# VoltageRegulatorShield.net
KiCad netlist of a schematic drawn in Altium Designer
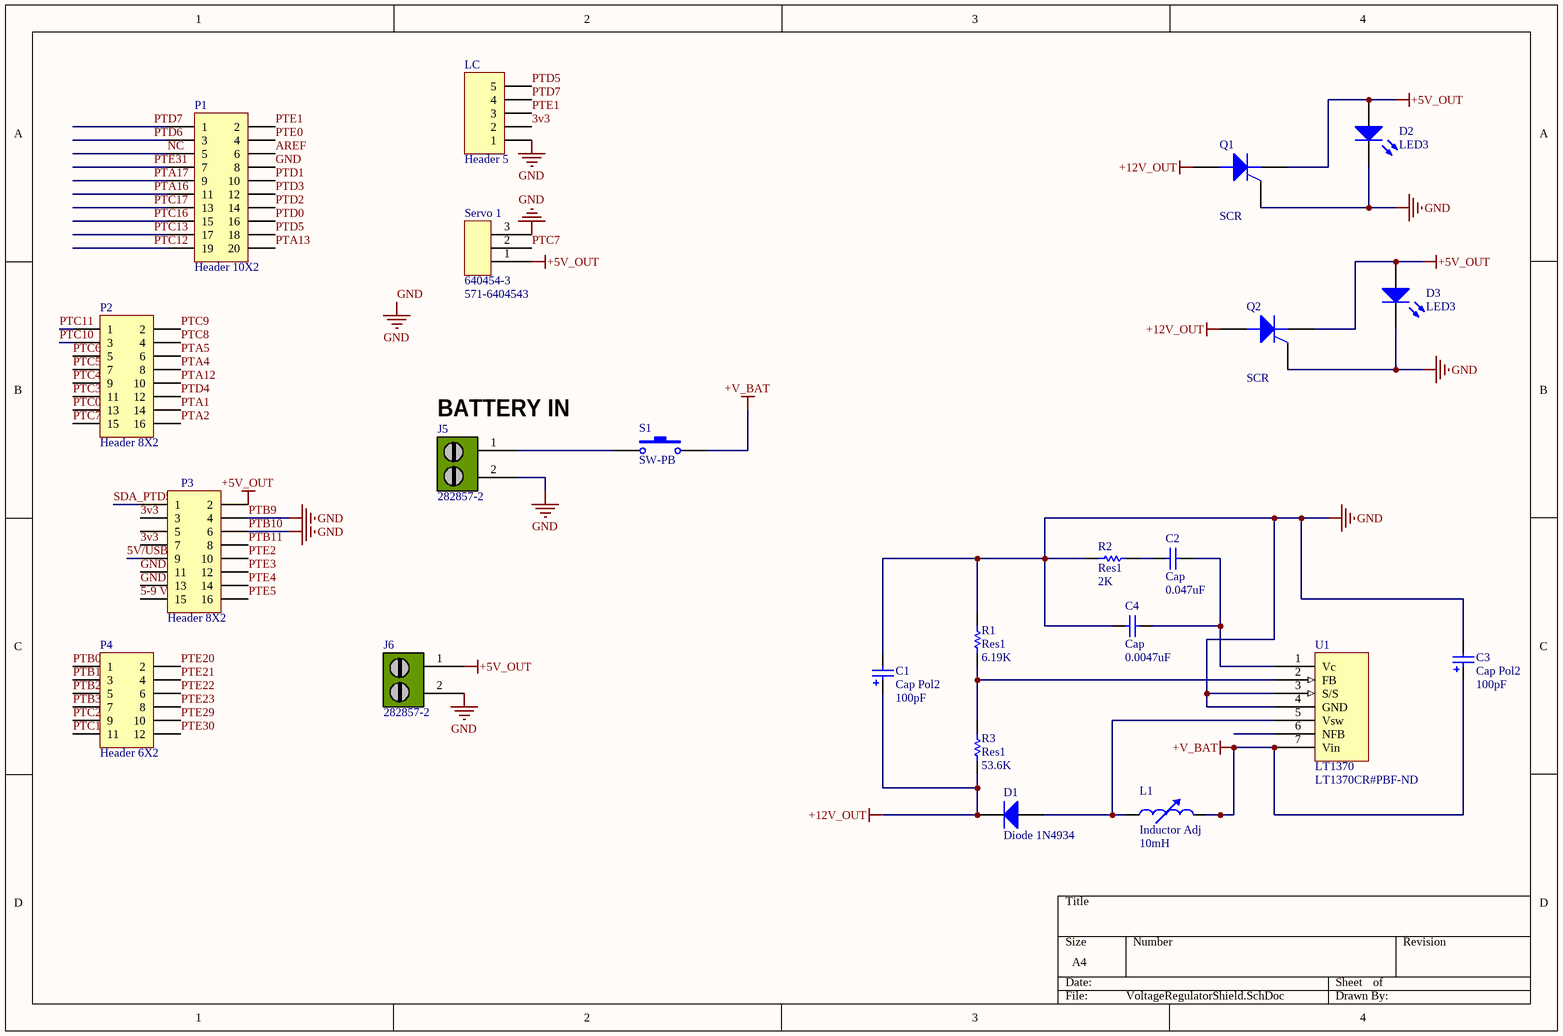
[diagram p0: VoltageRegulatorShield.SchDoc]

(export (version "E")
  (design (tool "Eeschema 10.0.6"))
  (components
    (comp (ref "C1")
      (value "Cap Pol2")
      (footprint "POLAR0.8")
      (description "Polarized Capacitor (Axial)")
      (fields (field (name "ALTIUM_VALUE") "100pF") (field (name "PUBLISHER") "Altium Limited"))
      (libsource (lib "Miscellaneous Devices") (part "Cap Pol2"))
    )
    (comp (ref "C2")
      (value "Cap")
      (footprint "RAD-0.3")
      (description "Capacitor")
      (fields (field (name "ALTIUM_VALUE") "0.047uF") (field (name "PUBLISHER") "Altium Limited"))
      (libsource (lib "Miscellaneous Devices") (part "Cap"))
    )
    (comp (ref "C3")
      (value "Cap Pol2")
      (footprint "POLAR0.8")
      (description "Polarized Capacitor (Axial)")
      (fields (field (name "ALTIUM_VALUE") "100pF") (field (name "PUBLISHER") "Altium Limited"))
      (libsource (lib "Miscellaneous Devices") (part "Cap Pol2"))
    )
    (comp (ref "C4")
      (value "Cap")
      (footprint "RAD-0.3")
      (description "Capacitor")
      (fields (field (name "ALTIUM_VALUE") "0.0047uF") (field (name "PUBLISHER") "Altium Limited"))
      (libsource (lib "Miscellaneous Devices") (part "Cap"))
    )
    (comp (ref "D1")
      (value "Diode 1N4934")
      (footprint "DO-41")
      (description "1 Amp Fast Recovery Rectifier")
      (fields (field (name "PUBLISHER") "Altium Limited"))
      (libsource (lib "Miscellaneous Devices") (part "Diode 1N4934"))
    )
    (comp (ref "D2")
      (value "LED3")
      (footprint "3.5X2.8X1.9")
      (description "Typical BLUE SiC LED")
      (fields (field (name "PUBLISHER") "Altium Limited"))
      (libsource (lib "Miscellaneous Devices") (part "LED3"))
    )
    (comp (ref "D3")
      (value "LED3")
      (footprint "3.5X2.8X1.9")
      (description "Typical BLUE SiC LED")
      (fields (field (name "PUBLISHER") "Altium Limited"))
      (libsource (lib "Miscellaneous Devices") (part "LED3"))
    )
    (comp (ref "J5")
      (value "282857-2")
      (footprint "282857-2")
      (description "TERM BLOCK 2POS SIDE ENT 5.08MM")
      (fields (field (name "MANUFACTURER") "TE Connectivity") (field (name "VOLTAGE") "300V"))
      (libsource (lib "eConnector") (part "282857-2"))
    )
    (comp (ref "J6")
      (value "282857-2")
      (footprint "282857-2")
      (description "TERM BLOCK 2POS SIDE ENT 5.08MM")
      (fields (field (name "MANUFACTURER") "TE Connectivity") (field (name "VOLTAGE") "300V"))
      (libsource (lib "eConnector") (part "282857-2"))
    )
    (comp (ref "L1")
      (value "Inductor Adj")
      (footprint "AXIAL-0.8")
      (description "Adjustable Inductor")
      (fields (field (name "ALTIUM_VALUE") "10mH") (field (name "PUBLISHER") "Altium Limited"))
      (libsource (lib "Miscellaneous Devices") (part "Inductor Adj"))
    )
    (comp (ref "LC")
      (value "Header 5")
      (footprint "HDR1X5")
      (description "Header, 5-Pin")
      (fields (field (name "PUBLISHER") "Altium Limited"))
      (libsource (lib "Miscellaneous Connectors") (part "Header 5"))
    )
    (comp (ref "P1")
      (value "Header 10X2")
      (footprint "HDR2X10")
      (description "Header, 10-Pin, Dual row")
      (fields (field (name "PUBLISHER") "Altium Limited"))
      (libsource (lib "Miscellaneous Connectors") (part "Header 10X2"))
    )
    (comp (ref "P2")
      (value "Header 8X2")
      (footprint "HDR2X8")
      (description "Header, 8-Pin, Dual row")
      (fields (field (name "PUBLISHER") "Altium Limited"))
      (libsource (lib "Miscellaneous Connectors") (part "Header 8X2"))
    )
    (comp (ref "P3")
      (value "Header 8X2")
      (footprint "HDR2X8")
      (description "Header, 8-Pin, Dual row")
      (fields (field (name "PUBLISHER") "Altium Limited"))
      (libsource (lib "Miscellaneous Connectors") (part "Header 8X2"))
    )
    (comp (ref "P4")
      (value "Header 6X2")
      (footprint "HDR2X6")
      (description "Header, 6-Pin, Dual row")
      (fields (field (name "PUBLISHER") "Altium Limited"))
      (libsource (lib "Miscellaneous Connectors") (part "Header 6X2"))
    )
    (comp (ref "Q1")
      (value "SCR")
      (footprint "TO-220-AB")
      (description "Silicon Controlled Rectifier")
      (fields (field (name "PUBLISHER") "Altium Limited"))
      (libsource (lib "Miscellaneous Devices") (part "SCR"))
    )
    (comp (ref "Q2")
      (value "SCR")
      (footprint "TO-220-AB")
      (description "Silicon Controlled Rectifier")
      (fields (field (name "PUBLISHER") "Altium Limited"))
      (libsource (lib "Miscellaneous Devices") (part "SCR"))
    )
    (comp (ref "R1")
      (value "Res1")
      (footprint "AXIAL-0.3")
      (description "Resistor")
      (fields (field (name "ALTIUM_VALUE") "6.19K") (field (name "PUBLISHER") "Altium Limited"))
      (libsource (lib "Miscellaneous Devices") (part "Res1"))
    )
    (comp (ref "R2")
      (value "Res1")
      (footprint "AXIAL-0.3")
      (description "Resistor")
      (fields (field (name "ALTIUM_VALUE") "2K") (field (name "PUBLISHER") "Altium Limited"))
      (libsource (lib "Miscellaneous Devices") (part "Res1"))
    )
    (comp (ref "R3")
      (value "Res1")
      (footprint "AXIAL-0.3")
      (description "Resistor")
      (fields (field (name "ALTIUM_VALUE") "53.6K") (field (name "PUBLISHER") "Altium Limited"))
      (libsource (lib "Miscellaneous Devices") (part "Res1"))
    )
    (comp (ref "S1")
      (value "SW-PB")
      (footprint "SPST-2")
      (description "Switch")
      (fields (field (name "PUBLISHER") "Altium Limited"))
      (libsource (lib "Miscellaneous Devices") (part "SW-PB"))
    )
    (comp (ref "Servo 1")
      (value "640454-3")
      (footprint "6404543")
      (description "Headers & Wire Housings POLARIZED HEADER 3P Straight Post tin")
      (fields (field (name "SUPPLIER PART NUMBER 1") "571-6404543"))
      (libsource (lib "TE_Connectors") (part "640454-3"))
    )
    (comp (ref "U1")
      (value "LT1370")
      (footprint "DDPak7")
      (fields (field (name "SUPPLIER PART NUMBER 1") "LT1370CR#PBF-ND"))
      (libsource (lib "Switching_Regulators") (part "LT1370"))
    )
  )
  (nets
    (net (code "1") (name "+5V_OUT") (class "Default")
      (node (ref "D2") (pin "1") (pinfunction "A_1") (pintype "passive"))
      (node (ref "D3") (pin "1") (pinfunction "A_1") (pintype "passive"))
      (node (ref "J6") (pin "1") (pinfunction "1_1") (pintype "passive"))
      (node (ref "P3") (pin "2") (pinfunction "2_2") (pintype "passive"))
      (node (ref "Q1") (pin "3") (pinfunction "K_3") (pintype "passive"))
      (node (ref "Q2") (pin "3") (pinfunction "K_3") (pintype "passive"))
      (node (ref "Servo 1") (pin "1") (pinfunction "1_1") (pintype "passive"))
    )
    (net (code "2") (name "+12V_OUT") (class "Default")
      (node (ref "C1") (pin "1") (pinfunction "1_1") (pintype "passive"))
      (node (ref "D1") (pin "2") (pinfunction "K_2") (pintype "passive"))
      (node (ref "Q1") (pin "1") (pinfunction "A_1") (pintype "passive"))
      (node (ref "Q2") (pin "1") (pinfunction "A_1") (pintype "passive"))
      (node (ref "R3") (pin "2") (pinfunction "2_2") (pintype "passive"))
    )
    (net (code "3") (name "+V_BAT") (class "Default")
      (node (ref "C3") (pin "1") (pinfunction "1_1") (pintype "passive"))
      (node (ref "L1") (pin "2") (pinfunction "2_2") (pintype "passive"))
      (node (ref "S1") (pin "2") (pinfunction "2_2") (pintype "passive"))
      (node (ref "U1") (pin "7") (pinfunction "Vin_7") (pintype "power_in"))
    )
    (net (code "4") (name "/3v3") (class "Default")
      (node (ref "LC") (pin "2") (pinfunction "2_2") (pintype "passive"))
      (node (ref "P3") (pin "3") (pinfunction "3_3") (pintype "passive"))
      (node (ref "P3") (pin "7") (pinfunction "7_7") (pintype "passive"))
    )
    (net (code "5") (name "/5-9 Vin") (class "Default")
      (node (ref "P3") (pin "15") (pinfunction "15_15") (pintype "passive"))
    )
    (net (code "6") (name "/5V{slash}USB") (class "Default")
      (node (ref "P3") (pin "9") (pinfunction "9_9") (pintype "passive"))
    )
    (net (code "7") (name "/AREF") (class "Default")
      (node (ref "P1") (pin "6") (pinfunction "6_6") (pintype "passive"))
    )
    (net (code "8") (name "/NC") (class "Default")
      (node (ref "P1") (pin "5") (pinfunction "5_5") (pintype "passive"))
    )
    (net (code "9") (name "/PTA1") (class "Default")
      (node (ref "P2") (pin "14") (pinfunction "14_14") (pintype "passive"))
    )
    (net (code "10") (name "/PTA2") (class "Default")
      (node (ref "P2") (pin "16") (pinfunction "16_16") (pintype "passive"))
    )
    (net (code "11") (name "/PTA4") (class "Default")
      (node (ref "P2") (pin "8") (pinfunction "8_8") (pintype "passive"))
    )
    (net (code "12") (name "/PTA5") (class "Default")
      (node (ref "P2") (pin "6") (pinfunction "6_6") (pintype "passive"))
    )
    (net (code "13") (name "/PTA12") (class "Default")
      (node (ref "P2") (pin "10") (pinfunction "10_10") (pintype "passive"))
    )
    (net (code "14") (name "/PTA13") (class "Default")
      (node (ref "P1") (pin "20") (pinfunction "20_20") (pintype "passive"))
    )
    (net (code "15") (name "/PTA16") (class "Default")
      (node (ref "P1") (pin "11") (pinfunction "11_11") (pintype "passive"))
    )
    (net (code "16") (name "/PTA17") (class "Default")
      (node (ref "P1") (pin "9") (pinfunction "9_9") (pintype "passive"))
    )
    (net (code "17") (name "/PTB0") (class "Default")
      (node (ref "P4") (pin "1") (pinfunction "1_1") (pintype "passive"))
    )
    (net (code "18") (name "/PTB1") (class "Default")
      (node (ref "P4") (pin "3") (pinfunction "3_3") (pintype "passive"))
    )
    (net (code "19") (name "/PTB2") (class "Default")
      (node (ref "P4") (pin "5") (pinfunction "5_5") (pintype "passive"))
    )
    (net (code "20") (name "/PTB3") (class "Default")
      (node (ref "P4") (pin "7") (pinfunction "7_7") (pintype "passive"))
    )
    (net (code "21") (name "/PTB11") (class "Default")
      (node (ref "P3") (pin "8") (pinfunction "8_8") (pintype "passive"))
    )
    (net (code "22") (name "/PTC0") (class "Default")
      (node (ref "P2") (pin "13") (pinfunction "13_13") (pintype "passive"))
    )
    (net (code "23") (name "/PTC1") (class "Default")
      (node (ref "P4") (pin "11") (pinfunction "11_11") (pintype "passive"))
    )
    (net (code "24") (name "/PTC2") (class "Default")
      (node (ref "P4") (pin "9") (pinfunction "9_9") (pintype "passive"))
    )
    (net (code "25") (name "/PTC3") (class "Default")
      (node (ref "P2") (pin "11") (pinfunction "11_11") (pintype "passive"))
    )
    (net (code "26") (name "/PTC4") (class "Default")
      (node (ref "P2") (pin "9") (pinfunction "9_9") (pintype "passive"))
    )
    (net (code "27") (name "/PTC5") (class "Default")
      (node (ref "P2") (pin "7") (pinfunction "7_7") (pintype "passive"))
    )
    (net (code "28") (name "/PTC6") (class "Default")
      (node (ref "P2") (pin "5") (pinfunction "5_5") (pintype "passive"))
    )
    (net (code "29") (name "/PTC7") (class "Default")
      (node (ref "P2") (pin "15") (pinfunction "15_15") (pintype "passive"))
      (node (ref "Servo 1") (pin "2") (pinfunction "2_2") (pintype "passive"))
    )
    (net (code "30") (name "/PTC8") (class "Default")
      (node (ref "P2") (pin "4") (pinfunction "4_4") (pintype "passive"))
    )
    (net (code "31") (name "/PTC9") (class "Default")
      (node (ref "P2") (pin "2") (pinfunction "2_2") (pintype "passive"))
    )
    (net (code "32") (name "/PTC10") (class "Default")
      (node (ref "P2") (pin "3") (pinfunction "3_3") (pintype "passive"))
    )
    (net (code "33") (name "/PTC11") (class "Default")
      (node (ref "P2") (pin "1") (pinfunction "1_1") (pintype "passive"))
    )
    (net (code "34") (name "/PTC12") (class "Default")
      (node (ref "P1") (pin "19") (pinfunction "19_19") (pintype "passive"))
    )
    (net (code "35") (name "/PTC13") (class "Default")
      (node (ref "P1") (pin "17") (pinfunction "17_17") (pintype "passive"))
    )
    (net (code "36") (name "/PTC16") (class "Default")
      (node (ref "P1") (pin "15") (pinfunction "15_15") (pintype "passive"))
    )
    (net (code "37") (name "/PTC17") (class "Default")
      (node (ref "P1") (pin "13") (pinfunction "13_13") (pintype "passive"))
    )
    (net (code "38") (name "/PTD0") (class "Default")
      (node (ref "P1") (pin "16") (pinfunction "16_16") (pintype "passive"))
    )
    (net (code "39") (name "/PTD1") (class "Default")
      (node (ref "P1") (pin "10") (pinfunction "10_10") (pintype "passive"))
    )
    (net (code "40") (name "/PTD2") (class "Default")
      (node (ref "P1") (pin "14") (pinfunction "14_14") (pintype "passive"))
    )
    (net (code "41") (name "/PTD3") (class "Default")
      (node (ref "P1") (pin "12") (pinfunction "12_12") (pintype "passive"))
    )
    (net (code "42") (name "/PTD4") (class "Default")
      (node (ref "P2") (pin "12") (pinfunction "12_12") (pintype "passive"))
    )
    (net (code "43") (name "/PTD5") (class "Default")
      (node (ref "LC") (pin "5") (pinfunction "5_5") (pintype "passive"))
      (node (ref "P1") (pin "18") (pinfunction "18_18") (pintype "passive"))
    )
    (net (code "44") (name "/PTD6") (class "Default")
      (node (ref "P1") (pin "3") (pinfunction "3_3") (pintype "passive"))
    )
    (net (code "45") (name "/PTD7") (class "Default")
      (node (ref "LC") (pin "4") (pinfunction "4_4") (pintype "passive"))
      (node (ref "P1") (pin "1") (pinfunction "1_1") (pintype "passive"))
    )
    (net (code "46") (name "/PTE0") (class "Default")
      (node (ref "P1") (pin "4") (pinfunction "4_4") (pintype "passive"))
    )
    (net (code "47") (name "/PTE1") (class "Default")
      (node (ref "LC") (pin "3") (pinfunction "3_3") (pintype "passive"))
      (node (ref "P1") (pin "2") (pinfunction "2_2") (pintype "passive"))
    )
    (net (code "48") (name "/PTE2") (class "Default")
      (node (ref "P3") (pin "10") (pinfunction "10_10") (pintype "passive"))
    )
    (net (code "49") (name "/PTE3") (class "Default")
      (node (ref "P3") (pin "12") (pinfunction "12_12") (pintype "passive"))
    )
    (net (code "50") (name "/PTE4") (class "Default")
      (node (ref "P3") (pin "14") (pinfunction "14_14") (pintype "passive"))
    )
    (net (code "51") (name "/PTE5") (class "Default")
      (node (ref "P3") (pin "16") (pinfunction "16_16") (pintype "passive"))
    )
    (net (code "52") (name "/PTE20") (class "Default")
      (node (ref "P4") (pin "2") (pinfunction "2_2") (pintype "passive"))
    )
    (net (code "53") (name "/PTE21") (class "Default")
      (node (ref "P4") (pin "4") (pinfunction "4_4") (pintype "passive"))
    )
    (net (code "54") (name "/PTE22") (class "Default")
      (node (ref "P4") (pin "6") (pinfunction "6_6") (pintype "passive"))
    )
    (net (code "55") (name "/PTE23") (class "Default")
      (node (ref "P4") (pin "8") (pinfunction "8_8") (pintype "passive"))
    )
    (net (code "56") (name "/PTE29") (class "Default")
      (node (ref "P4") (pin "10") (pinfunction "10_10") (pintype "passive"))
    )
    (net (code "57") (name "/PTE30") (class "Default")
      (node (ref "P4") (pin "12") (pinfunction "12_12") (pintype "passive"))
    )
    (net (code "58") (name "/PTE31") (class "Default")
      (node (ref "P1") (pin "7") (pinfunction "7_7") (pintype "passive"))
    )
    (net (code "59") (name "/SDA_PTD5") (class "Default")
      (node (ref "P3") (pin "1") (pinfunction "1_1") (pintype "passive"))
    )
    (net (code "60") (name "GND") (class "Default")
      (node (ref "C1") (pin "2") (pinfunction "2_2") (pintype "passive"))
      (node (ref "C3") (pin "2") (pinfunction "2_2") (pintype "passive"))
      (node (ref "C4") (pin "1") (pinfunction "1_1") (pintype "passive"))
      (node (ref "D2") (pin "2") (pinfunction "K_2") (pintype "passive"))
      (node (ref "D3") (pin "2") (pinfunction "K_2") (pintype "passive"))
      (node (ref "J5") (pin "2") (pinfunction "2_2") (pintype "passive"))
      (node (ref "J6") (pin "2") (pinfunction "2_2") (pintype "passive"))
      (node (ref "LC") (pin "1") (pinfunction "1_1") (pintype "passive"))
      (node (ref "P1") (pin "8") (pinfunction "8_8") (pintype "passive"))
      (node (ref "P3") (pin "11") (pinfunction "11_11") (pintype "passive"))
      (node (ref "P3") (pin "13") (pinfunction "13_13") (pintype "passive"))
      (node (ref "P3") (pin "4") (pinfunction "4_4") (pintype "passive"))
      (node (ref "P3") (pin "6") (pinfunction "6_6") (pintype "passive"))
      (node (ref "Q1") (pin "2") (pinfunction "G_2") (pintype "passive"))
      (node (ref "Q2") (pin "2") (pinfunction "G_2") (pintype "passive"))
      (node (ref "R1") (pin "1") (pinfunction "1_1") (pintype "passive"))
      (node (ref "R2") (pin "1") (pinfunction "1_1") (pintype "passive"))
      (node (ref "Servo 1") (pin "3") (pinfunction "3_3") (pintype "passive"))
      (node (ref "U1") (pin "3") (pinfunction "S/S_3") (pintype "input"))
      (node (ref "U1") (pin "4") (pinfunction "GND_4") (pintype "power_in"))
    )
    (net (code "61") (name "Net-(C2-Pad1)") (class "Default")
      (node (ref "C2") (pin "1") (pinfunction "1_1") (pintype "passive"))
      (node (ref "R2") (pin "2") (pinfunction "2_2") (pintype "passive"))
    )
    (net (code "62") (name "Net-(D1-A)") (class "Default")
      (node (ref "D1") (pin "1") (pinfunction "A_1") (pintype "passive"))
      (node (ref "L1") (pin "1") (pinfunction "1_1") (pintype "passive"))
      (node (ref "U1") (pin "5") (pinfunction "Vsw_5") (pintype "power_in"))
    )
    (net (code "63") (name "Net-(J5-Pad1)") (class "Default")
      (node (ref "J5") (pin "1") (pinfunction "1_1") (pintype "passive"))
      (node (ref "S1") (pin "1") (pinfunction "1_1") (pintype "passive"))
    )
    (net (code "64") (name "Net-(U1-FB)") (class "Default")
      (node (ref "R1") (pin "2") (pinfunction "2_2") (pintype "passive"))
      (node (ref "R3") (pin "1") (pinfunction "1_1") (pintype "passive"))
      (node (ref "U1") (pin "2") (pinfunction "FB_2") (pintype "input"))
    )
    (net (code "65") (name "Net-(U1-Vc)") (class "Default")
      (node (ref "C2") (pin "2") (pinfunction "2_2") (pintype "passive"))
      (node (ref "C4") (pin "2") (pinfunction "2_2") (pintype "passive"))
      (node (ref "U1") (pin "1") (pinfunction "Vc_1") (pintype "power_in"))
    )
    (net (code "66") (name "unconnected-(P3-Pad5)") (class "Default")
      (node (ref "P3") (pin "5") (pinfunction "5_5") (pintype "passive"))
    )
    (net (code "67") (name "unconnected-(U1-NFB-Pad6)") (class "Default")
      (node (ref "U1") (pin "6") (pinfunction "NFB_6") (pintype "open_collector"))
    )
  )
)
